# Schematics.net
KiCad netlist of a schematic drawn in EasyEDA
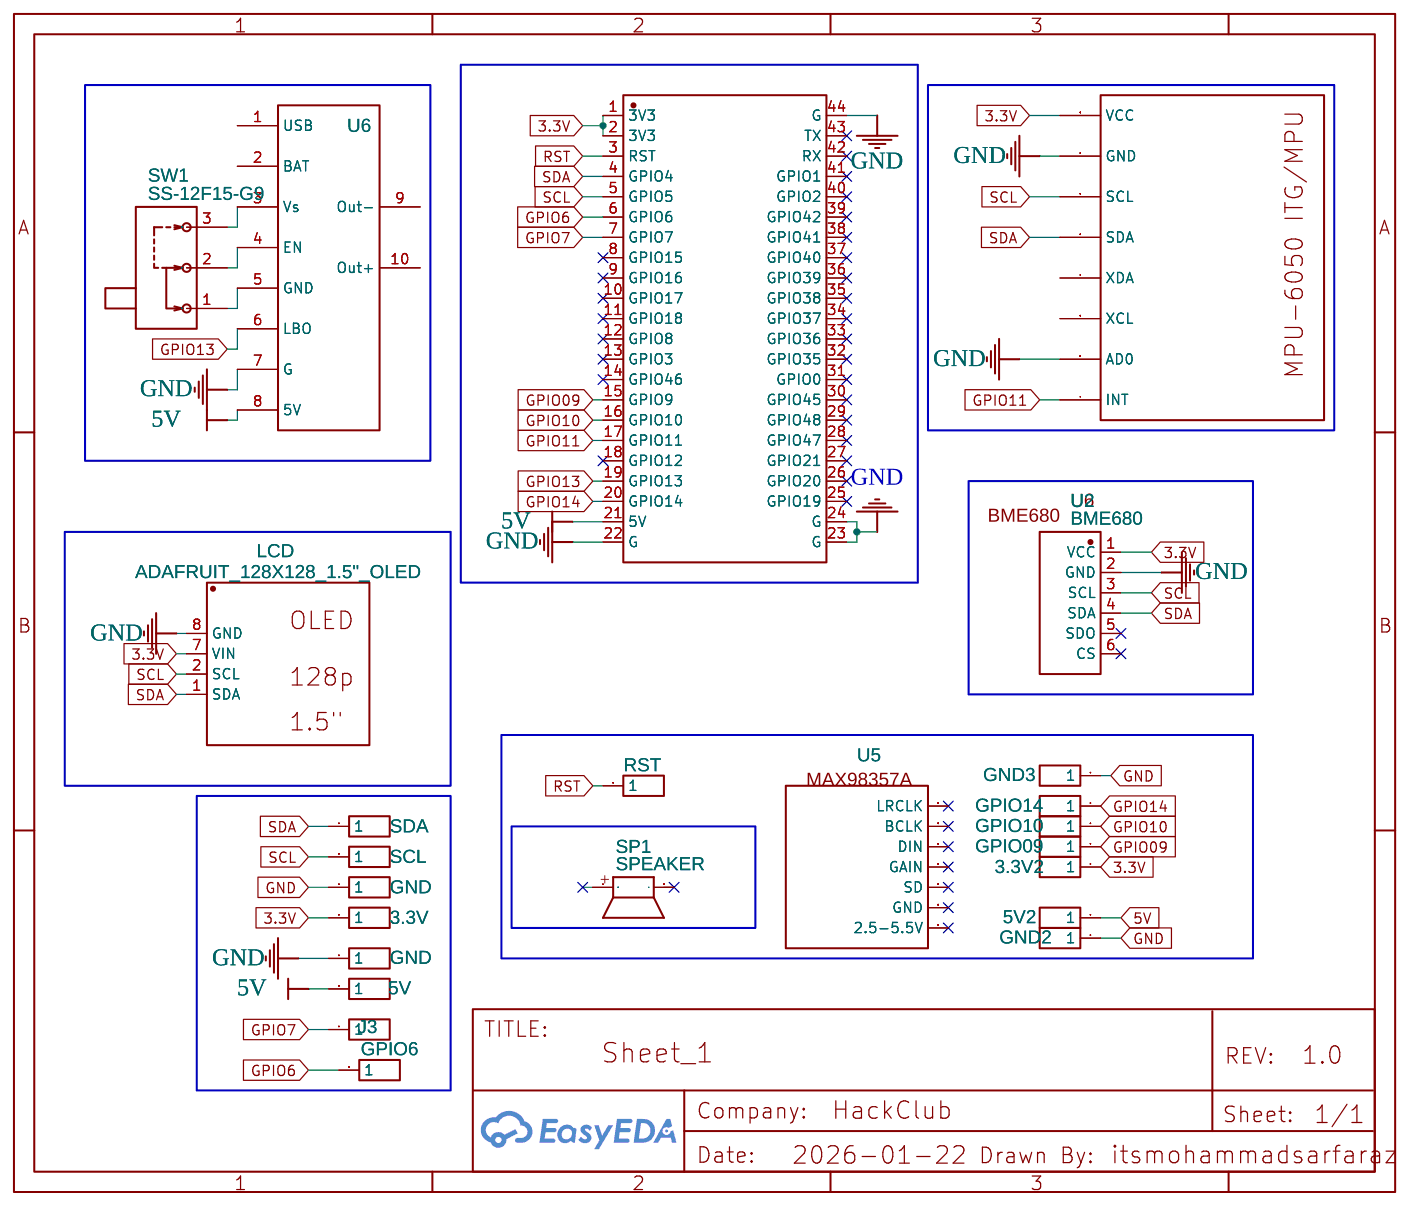
[diagram p0: schematic sheet]

(export (version "E")
  (design (tool "Eeschema 10.0.6"))
  (components
    (comp (ref "3.3V") (value "HDR-M-2.54_1x1") (libsource (lib "") (part "HDR-M-2.54_1x1_8")))
    (comp (ref "3.3V2") (value "HDR-M-2.54_1x1") (libsource (lib "") (part "HDR-M-2.54_1x1_1")))
    (comp (ref "5V2") (value "HDR-M-2.54_1x1") (libsource (lib "") (part "HDR-M-2.54_1x1_3")))
    (comp (ref "GND") (value "HDR-M-2.54_1x1") (libsource (lib "") (part "HDR-M-2.54_1x1_6")))
    (comp (ref "GND2") (value "HDR-M-2.54_1x1") (libsource (lib "") (part "HDR-M-2.54_1x1_4")))
    (comp (ref "GND3") (value "HDR-M-2.54_1x1") (libsource (lib "") (part "HDR-M-2.54_1x1_4")))
    (comp (ref "GPIO09") (value "HDR-M-2.54_1x1") (libsource (lib "") (part "HDR-M-2.54_1x1_2")))
    (comp (ref "GPIO10") (value "HDR-M-2.54_1x1") (libsource (lib "") (part "HDR-M-2.54_1x1_2")))
    (comp (ref "GPIO14") (value "HDR-M-2.54_1x1") (libsource (lib "") (part "HDR-M-2.54_1x1_2")))
    (comp (ref "J1") (value "GND") (libsource (lib "") (part "HDR-M-2.54_1x1")))
    (comp (ref "J2") (value "5V") (libsource (lib "") (part "HDR-M-2.54_1x1")))
    (comp (ref "J3") (value "HDR-M-2.54_1x1") (libsource (lib "") (part "HDR-M-2.54_1x1")))
    (comp (ref "J5") (value "GPIO6") (libsource (lib "") (part "HDR-M-2.54_1x1")))
    (comp (ref "LCD")
      (value "ADAFRUIT_128X128_1.5\"_OLED")
      (fields (field (name "Manufacturer Part") "MSP1503"))
      (libsource (lib "") (part "ADAFRUIT_128X128_1.5{dblquote}_OLED"))
    )
    (comp (ref "RST") (value "HDR-M-2.54_1x1") (libsource (lib "") (part "HDR-M-2.54_1x1_9")))
    (comp (ref "SCL") (value "HDR-M-2.54_1x1") (libsource (lib "") (part "HDR-M-2.54_1x1_7")))
    (comp (ref "SDA") (value "HDR-M-2.54_1x1") (libsource (lib "") (part "HDR-M-2.54_1x1_5")))
    (comp (ref "SP1") (value "SPEAKER") (libsource (lib "") (part "SPEAKER")))
    (comp (ref "SW1")
      (value "SS-12F15-G9")
      (fields (field (name "Manufacturer") "DEALON(德艺隆)"))
      (libsource (lib "") (part "SS-12F15-G9"))
    )
    (comp (ref "U1") (value "MPU-6050 ITG/MPU") (libsource (lib "") (part "MPU-6050 ITG/MPU")))
    (comp (ref "U2") (value "BME680") (libsource (lib "") (part "BME680")))
    (comp (ref "U4")
      (value "ESP32-S3-DevKitM-1U-N8")
      (fields
        (field (name "Manufacturer Part") "ESP32-S3-DevKitM-1")
        (field (name "Manufacturer") "Espressif")
      )
      (libsource (lib "") (part "ESP32-S3-DevKitM-1U-N8"))
    )
    (comp (ref "U5")
      (value "I2S MAX98357A MODULE")
      (fields (field (name "Manufacturer Part") "3006") (field (name "Manufacturer") "Adafruit"))
      (libsource (lib "") (part "I2S MAX98357A MODULE"))
    )
    (comp (ref "U6")
      (value "Adafruit Powerboost 1000C footprint")
      (fields (field (name "Manufacturer Part") "ada2465") (field (name "Manufacturer") "Adafruit"))
      (libsource (lib "") (part "Adafruit Powerboost 1000C footprint"))
    )
  )
  (nets
    (net (code "1") (name "3.3V") (class "Default")
      (node (ref "3.3V") (pin "1") (pinfunction "1_1") (pintype "input"))
      (node (ref "3.3V2") (pin "1") (pinfunction "1_1") (pintype "input"))
      (node (ref "LCD") (pin "7") (pinfunction "VIN_7") (pintype "unspecified"))
      (node (ref "U1") (pin "0") (pinfunction "VCC_0") (pintype "unspecified"))
      (node (ref "U2") (pin "1") (pinfunction "VCC_1") (pintype "unspecified"))
      (node (ref "U4") (pin "1") (pinfunction "3V3_1") (pintype "unspecified"))
      (node (ref "U4") (pin "2") (pinfunction "3V3_2") (pintype "unspecified"))
    )
    (net (code "2") (name "5V") (class "Default")
      (node (ref "5V2") (pin "1") (pinfunction "1_1") (pintype "input"))
      (node (ref "J2") (pin "1") (pinfunction "1_1") (pintype "input"))
      (node (ref "U4") (pin "21") (pinfunction "5V_21") (pintype "unspecified"))
      (node (ref "U6") (pin "8") (pinfunction "5V_8") (pintype "unspecified"))
    )
    (net (code "3") (name "GND") (class "Default")
      (node (ref "GND") (pin "1") (pinfunction "1_1") (pintype "input"))
      (node (ref "GND2") (pin "1") (pinfunction "1_1") (pintype "input"))
      (node (ref "GND3") (pin "1") (pinfunction "1_1") (pintype "input"))
      (node (ref "J1") (pin "1") (pinfunction "1_1") (pintype "input"))
      (node (ref "LCD") (pin "8") (pinfunction "GND_8") (pintype "unspecified"))
      (node (ref "U1") (pin "1") (pinfunction "GND_1") (pintype "unspecified"))
      (node (ref "U1") (pin "6") (pinfunction "AD0_6") (pintype "unspecified"))
      (node (ref "U2") (pin "2") (pinfunction "GND_2") (pintype "unspecified"))
      (node (ref "U4") (pin "22") (pinfunction "G_22") (pintype "unspecified"))
      (node (ref "U4") (pin "23") (pinfunction "G_23") (pintype "unspecified"))
      (node (ref "U4") (pin "24") (pinfunction "G_24") (pintype "unspecified"))
      (node (ref "U4") (pin "44") (pinfunction "G_44") (pintype "unspecified"))
      (node (ref "U6") (pin "7") (pinfunction "G_7") (pintype "unspecified"))
    )
    (net (code "4") (name "GPIO6") (class "Default")
      (node (ref "J3") (pin "1") (pinfunction "1_1") (pintype "input"))
      (node (ref "U4") (pin "6") (pinfunction "GPIO6_6") (pintype "unspecified"))
    )
    (net (code "5") (name "GPIO7") (class "Default")
      (node (ref "J5") (pin "1") (pinfunction "1_1") (pintype "input"))
      (node (ref "U4") (pin "7") (pinfunction "GPIO7_7") (pintype "unspecified"))
    )
    (net (code "6") (name "GPIO09") (class "Default")
      (node (ref "GPIO09") (pin "1") (pinfunction "1_1") (pintype "input"))
      (node (ref "U4") (pin "15") (pinfunction "GPIO9_15") (pintype "unspecified"))
    )
    (net (code "7") (name "GPIO10") (class "Default")
      (node (ref "GPIO10") (pin "1") (pinfunction "1_1") (pintype "input"))
      (node (ref "U4") (pin "16") (pinfunction "GPIO10_16") (pintype "unspecified"))
    )
    (net (code "8") (name "GPIO11") (class "Default")
      (node (ref "U1") (pin "7") (pinfunction "INT_7") (pintype "unspecified"))
      (node (ref "U4") (pin "17") (pinfunction "GPIO11_17") (pintype "unspecified"))
    )
    (net (code "9") (name "GPIO13") (class "Default")
      (node (ref "U4") (pin "19") (pinfunction "GPIO13_19") (pintype "unspecified"))
      (node (ref "U6") (pin "6") (pinfunction "LBO_6") (pintype "unspecified"))
    )
    (net (code "10") (name "GPIO14") (class "Default")
      (node (ref "GPIO14") (pin "1") (pinfunction "1_1") (pintype "input"))
      (node (ref "U4") (pin "20") (pinfunction "GPIO14_20") (pintype "unspecified"))
    )
    (net (code "11") (name "Net-(U6-EN)") (class "Default")
      (node (ref "SW1") (pin "2") (pinfunction "2_2") (pintype "unspecified"))
      (node (ref "U6") (pin "4") (pinfunction "EN_4") (pintype "unspecified"))
    )
    (net (code "12") (name "Net-(U6-GND)") (class "Default")
      (node (ref "SW1") (pin "1") (pinfunction "1_1") (pintype "unspecified"))
      (node (ref "U6") (pin "5") (pinfunction "GND_5") (pintype "unspecified"))
    )
    (net (code "13") (name "Net-(U6-Vs)") (class "Default")
      (node (ref "SW1") (pin "3") (pinfunction "3_3") (pintype "unspecified"))
      (node (ref "U6") (pin "3") (pinfunction "Vs_3") (pintype "unspecified"))
    )
    (net (code "14") (name "RST") (class "Default")
      (node (ref "RST") (pin "1") (pinfunction "1_1") (pintype "input"))
      (node (ref "U4") (pin "3") (pinfunction "RST_3") (pintype "unspecified"))
    )
    (net (code "15") (name "SCL") (class "Default")
      (node (ref "LCD") (pin "2") (pinfunction "SCL_2") (pintype "unspecified"))
      (node (ref "SCL") (pin "1") (pinfunction "1_1") (pintype "input"))
      (node (ref "U1") (pin "2") (pinfunction "SCL_2") (pintype "unspecified"))
      (node (ref "U2") (pin "3") (pinfunction "SCL_3") (pintype "unspecified"))
      (node (ref "U4") (pin "5") (pinfunction "GPIO5_5") (pintype "unspecified"))
    )
    (net (code "16") (name "SDA") (class "Default")
      (node (ref "LCD") (pin "1") (pinfunction "SDA_1") (pintype "unspecified"))
      (node (ref "SDA") (pin "1") (pinfunction "1_1") (pintype "input"))
      (node (ref "U1") (pin "3") (pinfunction "SDA_3") (pintype "unspecified"))
      (node (ref "U2") (pin "4") (pinfunction "SDA_4") (pintype "unspecified"))
      (node (ref "U4") (pin "4") (pinfunction "GPIO4_4") (pintype "unspecified"))
    )
    (net (code "17") (name "unconnected-(SP1-+-Pad1)") (class "Default")
      (node (ref "SP1") (pin "1") (pinfunction "+_1") (pintype "unspecified+no_connect"))
    )
    (net (code "18") (name "unconnected-(SP1---Pad2)") (class "Default")
      (node (ref "SP1") (pin "2") (pinfunction "-_2") (pintype "unspecified+no_connect"))
    )
    (net (code "19") (name "unconnected-(U1-XCL-Pad5)") (class "Default")
      (node (ref "U1") (pin "5") (pinfunction "XCL_5") (pintype "unspecified"))
    )
    (net (code "20") (name "unconnected-(U1-XDA-Pad4)") (class "Default")
      (node (ref "U1") (pin "4") (pinfunction "XDA_4") (pintype "unspecified"))
    )
    (net (code "21") (name "unconnected-(U2-CS-Pad6)") (class "Default")
      (node (ref "U2") (pin "6") (pinfunction "CS_6") (pintype "unspecified+no_connect"))
    )
    (net (code "22") (name "unconnected-(U2-SDO-Pad5)") (class "Default")
      (node (ref "U2") (pin "5") (pinfunction "SDO_5") (pintype "unspecified+no_connect"))
    )
    (net (code "23") (name "unconnected-(U4-GPIO0-Pad31)") (class "Default")
      (node (ref "U4") (pin "31") (pinfunction "GPIO0_31") (pintype "unspecified+no_connect"))
    )
    (net (code "24") (name "unconnected-(U4-GPIO1-Pad41)") (class "Default")
      (node (ref "U4") (pin "41") (pinfunction "GPIO1_41") (pintype "unspecified+no_connect"))
    )
    (net (code "25") (name "unconnected-(U4-GPIO2-Pad40)") (class "Default")
      (node (ref "U4") (pin "40") (pinfunction "GPIO2_40") (pintype "unspecified+no_connect"))
    )
    (net (code "26") (name "unconnected-(U4-GPIO3-Pad13)") (class "Default")
      (node (ref "U4") (pin "13") (pinfunction "GPIO3_13") (pintype "unspecified+no_connect"))
    )
    (net (code "27") (name "unconnected-(U4-GPIO8-Pad12)") (class "Default")
      (node (ref "U4") (pin "12") (pinfunction "GPIO8_12") (pintype "unspecified+no_connect"))
    )
    (net (code "28") (name "unconnected-(U4-GPIO12-Pad18)") (class "Default")
      (node (ref "U4") (pin "18") (pinfunction "GPIO12_18") (pintype "unspecified+no_connect"))
    )
    (net (code "29") (name "unconnected-(U4-GPIO15-Pad8)") (class "Default")
      (node (ref "U4") (pin "8") (pinfunction "GPIO15_8") (pintype "unspecified+no_connect"))
    )
    (net (code "30") (name "unconnected-(U4-GPIO16-Pad9)") (class "Default")
      (node (ref "U4") (pin "9") (pinfunction "GPIO16_9") (pintype "unspecified+no_connect"))
    )
    (net (code "31") (name "unconnected-(U4-GPIO17-Pad10)") (class "Default")
      (node (ref "U4") (pin "10") (pinfunction "GPIO17_10") (pintype "unspecified+no_connect"))
    )
    (net (code "32") (name "unconnected-(U4-GPIO18-Pad11)") (class "Default")
      (node (ref "U4") (pin "11") (pinfunction "GPIO18_11") (pintype "unspecified+no_connect"))
    )
    (net (code "33") (name "unconnected-(U4-GPIO19-Pad25)") (class "Default")
      (node (ref "U4") (pin "25") (pinfunction "GPIO19_25") (pintype "unspecified+no_connect"))
    )
    (net (code "34") (name "unconnected-(U4-GPIO20-Pad26)") (class "Default")
      (node (ref "U4") (pin "26") (pinfunction "GPIO20_26") (pintype "unspecified+no_connect"))
    )
    (net (code "35") (name "unconnected-(U4-GPIO21-Pad27)") (class "Default")
      (node (ref "U4") (pin "27") (pinfunction "GPIO21_27") (pintype "unspecified+no_connect"))
    )
    (net (code "36") (name "unconnected-(U4-GPIO35-Pad32)") (class "Default")
      (node (ref "U4") (pin "32") (pinfunction "GPIO35_32") (pintype "unspecified+no_connect"))
    )
    (net (code "37") (name "unconnected-(U4-GPIO36-Pad33)") (class "Default")
      (node (ref "U4") (pin "33") (pinfunction "GPIO36_33") (pintype "unspecified+no_connect"))
    )
    (net (code "38") (name "unconnected-(U4-GPIO37-Pad34)") (class "Default")
      (node (ref "U4") (pin "34") (pinfunction "GPIO37_34") (pintype "unspecified+no_connect"))
    )
    (net (code "39") (name "unconnected-(U4-GPIO38-Pad35)") (class "Default")
      (node (ref "U4") (pin "35") (pinfunction "GPIO38_35") (pintype "unspecified+no_connect"))
    )
    (net (code "40") (name "unconnected-(U4-GPIO39-Pad36)") (class "Default")
      (node (ref "U4") (pin "36") (pinfunction "GPIO39_36") (pintype "unspecified+no_connect"))
    )
    (net (code "41") (name "unconnected-(U4-GPIO40-Pad37)") (class "Default")
      (node (ref "U4") (pin "37") (pinfunction "GPIO40_37") (pintype "unspecified+no_connect"))
    )
    (net (code "42") (name "unconnected-(U4-GPIO41-Pad38)") (class "Default")
      (node (ref "U4") (pin "38") (pinfunction "GPIO41_38") (pintype "unspecified+no_connect"))
    )
    (net (code "43") (name "unconnected-(U4-GPIO42-Pad39)") (class "Default")
      (node (ref "U4") (pin "39") (pinfunction "GPIO42_39") (pintype "unspecified+no_connect"))
    )
    (net (code "44") (name "unconnected-(U4-GPIO45-Pad30)") (class "Default")
      (node (ref "U4") (pin "30") (pinfunction "GPIO45_30") (pintype "unspecified+no_connect"))
    )
    (net (code "45") (name "unconnected-(U4-GPIO46-Pad14)") (class "Default")
      (node (ref "U4") (pin "14") (pinfunction "GPIO46_14") (pintype "unspecified+no_connect"))
    )
    (net (code "46") (name "unconnected-(U4-GPIO47-Pad28)") (class "Default")
      (node (ref "U4") (pin "28") (pinfunction "GPIO47_28") (pintype "unspecified+no_connect"))
    )
    (net (code "47") (name "unconnected-(U4-GPIO48-Pad29)") (class "Default")
      (node (ref "U4") (pin "29") (pinfunction "GPIO48_29") (pintype "unspecified+no_connect"))
    )
    (net (code "48") (name "unconnected-(U4-RX-Pad42)") (class "Default")
      (node (ref "U4") (pin "42") (pinfunction "RX_42") (pintype "unspecified+no_connect"))
    )
    (net (code "49") (name "unconnected-(U4-TX-Pad43)") (class "Default")
      (node (ref "U4") (pin "43") (pinfunction "TX_43") (pintype "unspecified+no_connect"))
    )
    (net (code "50") (name "unconnected-(U5-2.5-5.5V-PadH7)") (class "Default")
      (node (ref "U5") (pin "H7") (pinfunction "2.5-5.5V_H7") (pintype "unspecified+no_connect"))
    )
    (net (code "51") (name "unconnected-(U5-BCLK-PadH2)") (class "Default")
      (node (ref "U5") (pin "H2") (pinfunction "BCLK_H2") (pintype "unspecified+no_connect"))
    )
    (net (code "52") (name "unconnected-(U5-DIN-PadH3)") (class "Default")
      (node (ref "U5") (pin "H3") (pinfunction "DIN_H3") (pintype "unspecified+no_connect"))
    )
    (net (code "53") (name "unconnected-(U5-GAIN-PadH4)") (class "Default")
      (node (ref "U5") (pin "H4") (pinfunction "GAIN_H4") (pintype "unspecified+no_connect"))
    )
    (net (code "54") (name "unconnected-(U5-GND-PadH6)") (class "Default")
      (node (ref "U5") (pin "H6") (pinfunction "GND_H6") (pintype "unspecified+no_connect"))
    )
    (net (code "55") (name "unconnected-(U5-LRCLK-PadH1)") (class "Default")
      (node (ref "U5") (pin "H1") (pinfunction "LRCLK_H1") (pintype "unspecified+no_connect"))
    )
    (net (code "56") (name "unconnected-(U5-SD-PadH5)") (class "Default")
      (node (ref "U5") (pin "H5") (pinfunction "SD_H5") (pintype "unspecified+no_connect"))
    )
    (net (code "57") (name "unconnected-(U6-BAT-Pad2)") (class "Default")
      (node (ref "U6") (pin "2") (pinfunction "BAT_2") (pintype "unspecified"))
    )
    (net (code "58") (name "unconnected-(U6-Out+-Pad10)") (class "Default")
      (node (ref "U6") (pin "10") (pinfunction "Out+_10") (pintype "unspecified"))
    )
    (net (code "59") (name "unconnected-(U6-Out--Pad9)") (class "Default")
      (node (ref "U6") (pin "9") (pinfunction "Out-_9") (pintype "unspecified"))
    )
    (net (code "60") (name "unconnected-(U6-USB-Pad1)") (class "Default")
      (node (ref "U6") (pin "1") (pinfunction "USB_1") (pintype "unspecified"))
    )
  )
)
